# Telemetry_mainlayoutVer2.net
KiCad netlist of a schematic drawn in EAGLE
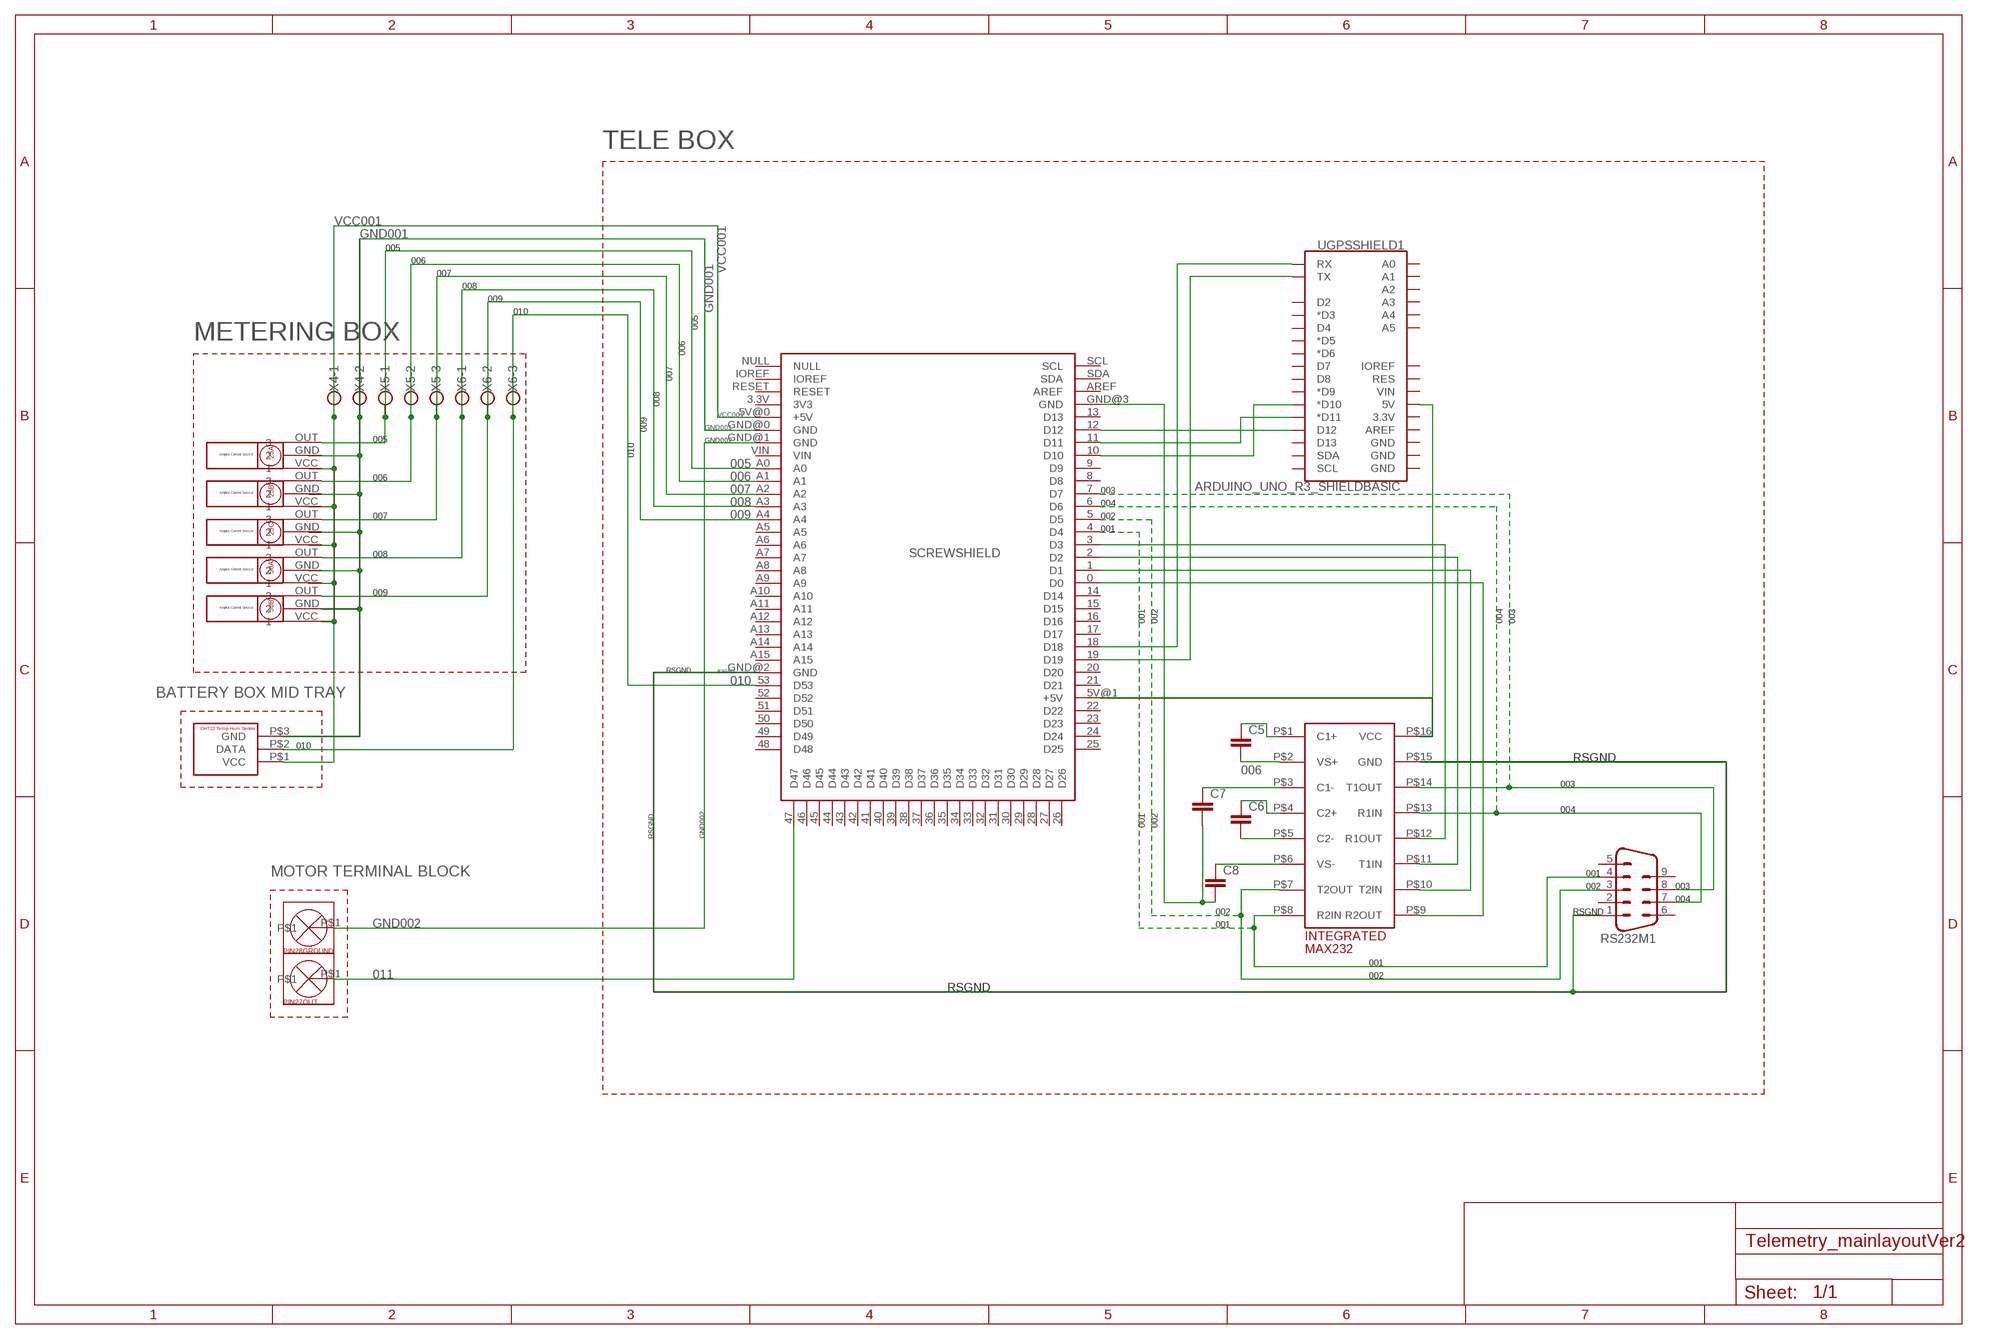
[diagram p0: schematic, sheet 1]

(export (version "E")
  (design (tool "Eeschema 10.0.6"))
  (components
    (comp (ref "25A")
      (value "AMPLOC-CS")
      (footprint "eagle-import:AMPLOC")
      (libsource (lib "eagle-import") (part "AMPLOC-CS"))
    )
    (comp (ref "25B")
      (value "AMPLOC-CS")
      (footprint "eagle-import:AMPLOC")
      (libsource (lib "eagle-import") (part "AMPLOC-CS"))
    )
    (comp (ref "25C")
      (value "AMPLOC-CS")
      (footprint "eagle-import:AMPLOC")
      (libsource (lib "eagle-import") (part "AMPLOC-CS"))
    )
    (comp (ref "50A")
      (value "AMPLOC-CS")
      (footprint "eagle-import:AMPLOC")
      (libsource (lib "eagle-import") (part "AMPLOC-CS"))
    )
    (comp (ref "50B")
      (value "AMPLOC-CS")
      (footprint "eagle-import:AMPLOC")
      (libsource (lib "eagle-import") (part "AMPLOC-CS"))
    )
    (comp (ref "C5")
      (value "C2,5-3")
      (footprint "eagle-import:C2.5-3")
      (libsource (lib "eagle-import") (part "C2,5-3"))
    )
    (comp (ref "C6")
      (value "C2,5-3")
      (footprint "eagle-import:C2.5-3")
      (libsource (lib "eagle-import") (part "C2,5-3"))
    )
    (comp (ref "C7")
      (value "C2,5-3")
      (footprint "eagle-import:C2.5-3")
      (libsource (lib "eagle-import") (part "C2,5-3"))
    )
    (comp (ref "C8")
      (value "C2,5-3")
      (footprint "eagle-import:C2.5-3")
      (libsource (lib "eagle-import") (part "C2,5-3"))
    )
    (comp (ref "INTEGRATED")
      (value "MAX232TELE")
      (footprint "eagle-import:DIP16")
      (libsource (lib "eagle-import") (part "MAX232TELE"))
    )
    (comp (ref "PIN27OUT")
      (value "SCREWTERMINAL")
      (footprint "eagle-import:SCREWTERMINAL")
      (libsource (lib "eagle-import") (part "SCREWTERMINAL"))
    )
    (comp (ref "PIN28GROUND")
      (value "SCREWTERMINAL")
      (footprint "eagle-import:SCREWTERMINAL")
      (libsource (lib "eagle-import") (part "SCREWTERMINAL"))
    )
    (comp (ref "RS232M1")
      (value "M09HP")
      (footprint "eagle-import:M09HP")
      (libsource (lib "eagle-import") (part "M09HP"))
    )
    (comp (ref "SCREWSHIELD")
      (value "PSCREWBPROTOSCREWSHIELD")
      (footprint "eagle-import:ARDUINO_MEGA")
      (libsource (lib "eagle-import") (part "PSCREWBPROTOSCREWSHIELD"))
    )
    (comp (ref "U$8")
      (value "DHT22")
      (footprint "eagle-import:DHT22")
      (libsource (lib "eagle-import") (part "DHT22"))
    )
    (comp (ref "UGPSSHIELD1")
      (value "ARDUINO_UNO_R3_SHIELDBASIC")
      (footprint "eagle-import:UNO_R3_SHIELD")
      (libsource (lib "eagle-import") (part "ARDUINO_UNO_R3_SHIELDBASIC"))
    )
    (comp (ref "X4")
      (value "W237-102")
      (footprint "eagle-import:W237-102")
      (fields (field (name "MPN") "237-102"))
      (libsource (lib "eagle-import") (part "W237-102"))
    )
    (comp (ref "X5")
      (value "W237-103")
      (footprint "eagle-import:W237-103")
      (fields (field (name "MPN") "237-103"))
      (libsource (lib "eagle-import") (part "W237-103"))
    )
    (comp (ref "X6")
      (value "W237-103")
      (footprint "eagle-import:W237-103")
      (fields (field (name "MPN") "237-103"))
      (libsource (lib "eagle-import") (part "W237-103"))
    )
  )
  (nets
    (net (code "1") (name "Net-(25A-1)") (class "Default")
      (node (ref "25A") (pin "VCC") (pinfunction "1_VCC") (pintype "bidirectional"))
      (node (ref "25B") (pin "VCC") (pinfunction "1_VCC") (pintype "bidirectional"))
      (node (ref "25C") (pin "VCC") (pinfunction "1_VCC") (pintype "bidirectional"))
      (node (ref "50A") (pin "VCC") (pinfunction "1_VCC") (pintype "bidirectional"))
      (node (ref "50B") (pin "VCC") (pinfunction "1_VCC") (pintype "bidirectional"))
      (node (ref "SCREWSHIELD") (pin "5V@0") (pinfunction "+5V_5V@0") (pintype "bidirectional"))
      (node (ref "U$8") (pin "P$1") (pinfunction "VCC_P$1") (pintype "bidirectional"))
      (node (ref "X4") (pin "1") (pinfunction "KL_1") (pintype "passive"))
    )
    (net (code "2") (name "Net-(25A-2)") (class "Default")
      (node (ref "25A") (pin "GND") (pinfunction "2_GND") (pintype "bidirectional"))
      (node (ref "25B") (pin "GND") (pinfunction "2_GND") (pintype "bidirectional"))
      (node (ref "25C") (pin "GND") (pinfunction "2_GND") (pintype "bidirectional"))
      (node (ref "50A") (pin "GND") (pinfunction "2_GND") (pintype "bidirectional"))
      (node (ref "50B") (pin "GND") (pinfunction "2_GND") (pintype "bidirectional"))
      (node (ref "SCREWSHIELD") (pin "GND@0") (pinfunction "GND_GND@0") (pintype "bidirectional"))
      (node (ref "U$8") (pin "P$3") (pinfunction "GND_P$3") (pintype "bidirectional"))
      (node (ref "X4") (pin "2") (pinfunction "KL_2") (pintype "passive"))
    )
    (net (code "3") (name "Net-(25A-3)") (class "Default")
      (node (ref "25A") (pin "OUT") (pinfunction "3_OUT") (pintype "bidirectional"))
      (node (ref "SCREWSHIELD") (pin "A0") (pinfunction "A0_A0") (pintype "bidirectional"))
      (node (ref "X5") (pin "1") (pinfunction "KL_1") (pintype "passive"))
    )
    (net (code "4") (name "Net-(25B-3)") (class "Default")
      (node (ref "25B") (pin "OUT") (pinfunction "3_OUT") (pintype "bidirectional"))
      (node (ref "SCREWSHIELD") (pin "A1") (pinfunction "A1_A1") (pintype "bidirectional"))
      (node (ref "X5") (pin "2") (pinfunction "KL_2") (pintype "passive"))
    )
    (net (code "5") (name "Net-(25C-3)") (class "Default")
      (node (ref "25C") (pin "OUT") (pinfunction "3_OUT") (pintype "bidirectional"))
      (node (ref "SCREWSHIELD") (pin "A2") (pinfunction "A2_A2") (pintype "bidirectional"))
      (node (ref "X5") (pin "3") (pinfunction "KL_3") (pintype "passive"))
    )
    (net (code "6") (name "Net-(50A-3)") (class "Default")
      (node (ref "50A") (pin "OUT") (pinfunction "3_OUT") (pintype "bidirectional"))
      (node (ref "SCREWSHIELD") (pin "A3") (pinfunction "A3_A3") (pintype "bidirectional"))
      (node (ref "X6") (pin "1") (pinfunction "KL_1") (pintype "passive"))
    )
    (net (code "7") (name "Net-(50B-3)") (class "Default")
      (node (ref "50B") (pin "OUT") (pinfunction "3_OUT") (pintype "bidirectional"))
      (node (ref "SCREWSHIELD") (pin "A4") (pinfunction "A4_A4") (pintype "bidirectional"))
      (node (ref "X6") (pin "2") (pinfunction "KL_2") (pintype "passive"))
    )
    (net (code "8") (name "Net-(C7-Pad2)") (class "Default")
      (node (ref "C7") (pin "2") (pinfunction "2_2") (pintype "passive"))
      (node (ref "C8") (pin "2") (pinfunction "2_2") (pintype "passive"))
      (node (ref "SCREWSHIELD") (pin "GND@3") (pinfunction "GND_GND@3") (pintype "bidirectional"))
    )
    (net (code "9") (name "Net-(INTEGRATED-C1+)") (class "Default")
      (node (ref "C5") (pin "1") (pinfunction "1_1") (pintype "passive"))
      (node (ref "INTEGRATED") (pin "P$1") (pinfunction "C1+_P$1") (pintype "bidirectional"))
    )
    (net (code "10") (name "Net-(INTEGRATED-C1-)") (class "Default")
      (node (ref "C7") (pin "1") (pinfunction "1_1") (pintype "passive"))
      (node (ref "INTEGRATED") (pin "P$3") (pinfunction "C1-_P$3") (pintype "bidirectional"))
    )
    (net (code "11") (name "Net-(INTEGRATED-C2+)") (class "Default")
      (node (ref "C6") (pin "1") (pinfunction "1_1") (pintype "passive"))
      (node (ref "INTEGRATED") (pin "P$4") (pinfunction "C2+_P$4") (pintype "bidirectional"))
    )
    (net (code "12") (name "Net-(INTEGRATED-C2-)") (class "Default")
      (node (ref "C6") (pin "2") (pinfunction "2_2") (pintype "passive"))
      (node (ref "INTEGRATED") (pin "P$5") (pinfunction "C2-_P$5") (pintype "bidirectional"))
    )
    (net (code "13") (name "Net-(INTEGRATED-GND)") (class "Default")
      (node (ref "INTEGRATED") (pin "P$15") (pinfunction "GND_P$15") (pintype "bidirectional"))
      (node (ref "RS232M1") (pin "1") (pinfunction "1_1") (pintype "passive"))
      (node (ref "SCREWSHIELD") (pin "GND@2") (pinfunction "GND_GND@2") (pintype "bidirectional"))
    )
    (net (code "14") (name "Net-(INTEGRATED-R1IN)") (class "Default")
      (node (ref "INTEGRATED") (pin "P$13") (pinfunction "R1IN_P$13") (pintype "bidirectional"))
      (node (ref "RS232M1") (pin "7") (pinfunction "7_7") (pintype "passive"))
      (node (ref "SCREWSHIELD") (pin "6") (pinfunction "D6_6") (pintype "bidirectional"))
    )
    (net (code "15") (name "Net-(INTEGRATED-R1OUT)") (class "Default")
      (node (ref "INTEGRATED") (pin "P$12") (pinfunction "R1OUT_P$12") (pintype "bidirectional"))
      (node (ref "SCREWSHIELD") (pin "3") (pinfunction "D3_3") (pintype "bidirectional"))
    )
    (net (code "16") (name "Net-(INTEGRATED-R2IN)") (class "Default")
      (node (ref "INTEGRATED") (pin "P$8") (pinfunction "R2IN_P$8") (pintype "bidirectional"))
      (node (ref "RS232M1") (pin "4") (pinfunction "4_4") (pintype "passive"))
      (node (ref "SCREWSHIELD") (pin "4") (pinfunction "D4_4") (pintype "bidirectional"))
    )
    (net (code "17") (name "Net-(INTEGRATED-R2OUT)") (class "Default")
      (node (ref "INTEGRATED") (pin "P$9") (pinfunction "R2OUT_P$9") (pintype "bidirectional"))
      (node (ref "SCREWSHIELD") (pin "0") (pinfunction "D0_0") (pintype "bidirectional"))
    )
    (net (code "18") (name "Net-(INTEGRATED-T1IN)") (class "Default")
      (node (ref "INTEGRATED") (pin "P$11") (pinfunction "T1IN_P$11") (pintype "bidirectional"))
      (node (ref "SCREWSHIELD") (pin "2") (pinfunction "D2_2") (pintype "bidirectional"))
    )
    (net (code "19") (name "Net-(INTEGRATED-T1OUT)") (class "Default")
      (node (ref "INTEGRATED") (pin "P$14") (pinfunction "T1OUT_P$14") (pintype "bidirectional"))
      (node (ref "RS232M1") (pin "8") (pinfunction "8_8") (pintype "passive"))
      (node (ref "SCREWSHIELD") (pin "7") (pinfunction "D7_7") (pintype "bidirectional"))
    )
    (net (code "20") (name "Net-(INTEGRATED-T2IN)") (class "Default")
      (node (ref "INTEGRATED") (pin "P$10") (pinfunction "T2IN_P$10") (pintype "bidirectional"))
      (node (ref "SCREWSHIELD") (pin "1") (pinfunction "D1_1") (pintype "bidirectional"))
    )
    (net (code "21") (name "Net-(INTEGRATED-T2OUT)") (class "Default")
      (node (ref "INTEGRATED") (pin "P$7") (pinfunction "T2OUT_P$7") (pintype "bidirectional"))
      (node (ref "RS232M1") (pin "3") (pinfunction "3_3") (pintype "passive"))
      (node (ref "SCREWSHIELD") (pin "5") (pinfunction "D5_5") (pintype "bidirectional"))
    )
    (net (code "22") (name "Net-(INTEGRATED-VCC)") (class "Default")
      (node (ref "INTEGRATED") (pin "P$16") (pinfunction "VCC_P$16") (pintype "bidirectional"))
      (node (ref "SCREWSHIELD") (pin "5V@1") (pinfunction "+5V_5V@1") (pintype "bidirectional"))
      (node (ref "UGPSSHIELD1") (pin "5V") (pinfunction "5V_5V") (pintype "bidirectional"))
    )
    (net (code "23") (name "Net-(INTEGRATED-VS+)") (class "Default")
      (node (ref "C5") (pin "2") (pinfunction "2_2") (pintype "passive"))
      (node (ref "INTEGRATED") (pin "P$2") (pinfunction "VS+_P$2") (pintype "bidirectional"))
    )
    (net (code "24") (name "Net-(INTEGRATED-VS-)") (class "Default")
      (node (ref "C8") (pin "1") (pinfunction "1_1") (pintype "passive"))
      (node (ref "INTEGRATED") (pin "P$6") (pinfunction "VS-_P$6") (pintype "bidirectional"))
    )
    (net (code "25") (name "Net-(PIN28GROUND-PadP$1)") (class "Default")
      (node (ref "PIN28GROUND") (pin "P$1") (pinfunction "P$1_P$1") (pintype "bidirectional"))
      (node (ref "SCREWSHIELD") (pin "GND@1") (pinfunction "GND_GND@1") (pintype "bidirectional"))
    )
    (net (code "26") (name "Net-(SCREWSHIELD-D10)") (class "Default")
      (node (ref "SCREWSHIELD") (pin "10") (pinfunction "D10_10") (pintype "bidirectional"))
      (node (ref "UGPSSHIELD1") (pin "D10") (pinfunction "*D10_D10") (pintype "bidirectional"))
    )
    (net (code "27") (name "Net-(SCREWSHIELD-D11)") (class "Default")
      (node (ref "SCREWSHIELD") (pin "11") (pinfunction "D11_11") (pintype "bidirectional"))
      (node (ref "UGPSSHIELD1") (pin "D11") (pinfunction "*D11_D11") (pintype "bidirectional"))
    )
    (net (code "28") (name "Net-(SCREWSHIELD-D12)") (class "Default")
      (node (ref "SCREWSHIELD") (pin "12") (pinfunction "D12_12") (pintype "bidirectional"))
      (node (ref "UGPSSHIELD1") (pin "D12") (pinfunction "D12_D12") (pintype "bidirectional"))
    )
    (net (code "29") (name "Net-(SCREWSHIELD-D18)") (class "Default")
      (node (ref "SCREWSHIELD") (pin "18") (pinfunction "D18_18") (pintype "bidirectional"))
      (node (ref "UGPSSHIELD1") (pin "RX") (pinfunction "RX_RX") (pintype "bidirectional"))
    )
    (net (code "30") (name "Net-(SCREWSHIELD-D19)") (class "Default")
      (node (ref "SCREWSHIELD") (pin "19") (pinfunction "D19_19") (pintype "bidirectional"))
      (node (ref "UGPSSHIELD1") (pin "TX") (pinfunction "TX_TX") (pintype "bidirectional"))
    )
    (net (code "31") (name "Net-(SCREWSHIELD-D47)") (class "Default")
      (node (ref "PIN27OUT") (pin "P$1") (pinfunction "P$1_P$1") (pintype "bidirectional"))
      (node (ref "SCREWSHIELD") (pin "47") (pinfunction "D47_47") (pintype "bidirectional"))
    )
    (net (code "32") (name "Net-(SCREWSHIELD-D53)") (class "Default")
      (node (ref "SCREWSHIELD") (pin "53") (pinfunction "D53_53") (pintype "bidirectional"))
      (node (ref "U$8") (pin "P$2") (pinfunction "DATA_P$2") (pintype "bidirectional"))
      (node (ref "X6") (pin "3") (pinfunction "KL_3") (pintype "passive"))
    )
    (net (code "33") (name "unconnected-(RS232M1-Pad2)") (class "Default")
      (node (ref "RS232M1") (pin "2") (pinfunction "2_2") (pintype "passive"))
    )
    (net (code "34") (name "unconnected-(RS232M1-Pad5)") (class "Default")
      (node (ref "RS232M1") (pin "5") (pinfunction "5_5") (pintype "passive"))
    )
    (net (code "35") (name "unconnected-(RS232M1-Pad6)") (class "Default")
      (node (ref "RS232M1") (pin "6") (pinfunction "6_6") (pintype "passive"))
    )
    (net (code "36") (name "unconnected-(RS232M1-Pad9)") (class "Default")
      (node (ref "RS232M1") (pin "9") (pinfunction "9_9") (pintype "passive"))
    )
    (net (code "37") (name "unconnected-(SCREWSHIELD-3V3-Pad3.3V)") (class "Default")
      (node (ref "SCREWSHIELD") (pin "3.3V") (pinfunction "3V3_3.3V") (pintype "bidirectional"))
    )
    (net (code "38") (name "unconnected-(SCREWSHIELD-D8-Pad8)") (class "Default")
      (node (ref "SCREWSHIELD") (pin "8") (pinfunction "D8_8") (pintype "bidirectional"))
    )
    (net (code "39") (name "unconnected-(SCREWSHIELD-D9-Pad9)") (class "Default")
      (node (ref "SCREWSHIELD") (pin "9") (pinfunction "D9_9") (pintype "bidirectional"))
    )
    (net (code "40") (name "unconnected-(SCREWSHIELD-D13-Pad13)") (class "Default")
      (node (ref "SCREWSHIELD") (pin "13") (pinfunction "D13_13") (pintype "bidirectional"))
    )
    (net (code "41") (name "unconnected-(SCREWSHIELD-D14-Pad14)") (class "Default")
      (node (ref "SCREWSHIELD") (pin "14") (pinfunction "D14_14") (pintype "bidirectional"))
    )
    (net (code "42") (name "unconnected-(SCREWSHIELD-D15-Pad15)") (class "Default")
      (node (ref "SCREWSHIELD") (pin "15") (pinfunction "D15_15") (pintype "bidirectional"))
    )
    (net (code "43") (name "unconnected-(SCREWSHIELD-D16-Pad16)") (class "Default")
      (node (ref "SCREWSHIELD") (pin "16") (pinfunction "D16_16") (pintype "bidirectional"))
    )
    (net (code "44") (name "unconnected-(SCREWSHIELD-D17-Pad17)") (class "Default")
      (node (ref "SCREWSHIELD") (pin "17") (pinfunction "D17_17") (pintype "bidirectional"))
    )
    (net (code "45") (name "unconnected-(SCREWSHIELD-D20-Pad20)") (class "Default")
      (node (ref "SCREWSHIELD") (pin "20") (pinfunction "D20_20") (pintype "bidirectional"))
    )
    (net (code "46") (name "unconnected-(SCREWSHIELD-D21-Pad21)") (class "Default")
      (node (ref "SCREWSHIELD") (pin "21") (pinfunction "D21_21") (pintype "bidirectional"))
    )
    (net (code "47") (name "unconnected-(SCREWSHIELD-D22-Pad22)") (class "Default")
      (node (ref "SCREWSHIELD") (pin "22") (pinfunction "D22_22") (pintype "bidirectional"))
    )
    (net (code "48") (name "unconnected-(SCREWSHIELD-D23-Pad23)") (class "Default")
      (node (ref "SCREWSHIELD") (pin "23") (pinfunction "D23_23") (pintype "bidirectional"))
    )
    (net (code "49") (name "unconnected-(SCREWSHIELD-D24-Pad24)") (class "Default")
      (node (ref "SCREWSHIELD") (pin "24") (pinfunction "D24_24") (pintype "bidirectional"))
    )
    (net (code "50") (name "unconnected-(SCREWSHIELD-D25-Pad25)") (class "Default")
      (node (ref "SCREWSHIELD") (pin "25") (pinfunction "D25_25") (pintype "bidirectional"))
    )
    (net (code "51") (name "unconnected-(SCREWSHIELD-D26-Pad26)") (class "Default")
      (node (ref "SCREWSHIELD") (pin "26") (pinfunction "D26_26") (pintype "bidirectional"))
    )
    (net (code "52") (name "unconnected-(SCREWSHIELD-D27-Pad27)") (class "Default")
      (node (ref "SCREWSHIELD") (pin "27") (pinfunction "D27_27") (pintype "bidirectional"))
    )
    (net (code "53") (name "unconnected-(SCREWSHIELD-D28-Pad28)") (class "Default")
      (node (ref "SCREWSHIELD") (pin "28") (pinfunction "D28_28") (pintype "bidirectional"))
    )
    (net (code "54") (name "unconnected-(SCREWSHIELD-D29-Pad29)") (class "Default")
      (node (ref "SCREWSHIELD") (pin "29") (pinfunction "D29_29") (pintype "bidirectional"))
    )
    (net (code "55") (name "unconnected-(SCREWSHIELD-D30-Pad30)") (class "Default")
      (node (ref "SCREWSHIELD") (pin "30") (pinfunction "D30_30") (pintype "bidirectional"))
    )
    (net (code "56") (name "unconnected-(SCREWSHIELD-D31-Pad31)") (class "Default")
      (node (ref "SCREWSHIELD") (pin "31") (pinfunction "D31_31") (pintype "bidirectional"))
    )
    (net (code "57") (name "unconnected-(SCREWSHIELD-D32-Pad32)") (class "Default")
      (node (ref "SCREWSHIELD") (pin "32") (pinfunction "D32_32") (pintype "bidirectional"))
    )
    (net (code "58") (name "unconnected-(SCREWSHIELD-D33-Pad33)") (class "Default")
      (node (ref "SCREWSHIELD") (pin "33") (pinfunction "D33_33") (pintype "bidirectional"))
    )
    (net (code "59") (name "unconnected-(SCREWSHIELD-D34-Pad34)") (class "Default")
      (node (ref "SCREWSHIELD") (pin "34") (pinfunction "D34_34") (pintype "bidirectional"))
    )
    (net (code "60") (name "unconnected-(SCREWSHIELD-D35-Pad35)") (class "Default")
      (node (ref "SCREWSHIELD") (pin "35") (pinfunction "D35_35") (pintype "bidirectional"))
    )
    (net (code "61") (name "unconnected-(SCREWSHIELD-D36-Pad36)") (class "Default")
      (node (ref "SCREWSHIELD") (pin "36") (pinfunction "D36_36") (pintype "bidirectional"))
    )
    (net (code "62") (name "unconnected-(SCREWSHIELD-D37-Pad37)") (class "Default")
      (node (ref "SCREWSHIELD") (pin "37") (pinfunction "D37_37") (pintype "bidirectional"))
    )
    (net (code "63") (name "unconnected-(SCREWSHIELD-D38-Pad38)") (class "Default")
      (node (ref "SCREWSHIELD") (pin "38") (pinfunction "D38_38") (pintype "bidirectional"))
    )
    (net (code "64") (name "unconnected-(SCREWSHIELD-D39-Pad39)") (class "Default")
      (node (ref "SCREWSHIELD") (pin "39") (pinfunction "D39_39") (pintype "bidirectional"))
    )
    (net (code "65") (name "unconnected-(SCREWSHIELD-D40-Pad40)") (class "Default")
      (node (ref "SCREWSHIELD") (pin "40") (pinfunction "D40_40") (pintype "bidirectional"))
    )
    (net (code "66") (name "unconnected-(SCREWSHIELD-D41-Pad41)") (class "Default")
      (node (ref "SCREWSHIELD") (pin "41") (pinfunction "D41_41") (pintype "bidirectional"))
    )
    (net (code "67") (name "unconnected-(SCREWSHIELD-D42-Pad42)") (class "Default")
      (node (ref "SCREWSHIELD") (pin "42") (pinfunction "D42_42") (pintype "bidirectional"))
    )
    (net (code "68") (name "unconnected-(SCREWSHIELD-D43-Pad43)") (class "Default")
      (node (ref "SCREWSHIELD") (pin "43") (pinfunction "D43_43") (pintype "bidirectional"))
    )
    (net (code "69") (name "unconnected-(SCREWSHIELD-D44-Pad44)") (class "Default")
      (node (ref "SCREWSHIELD") (pin "44") (pinfunction "D44_44") (pintype "bidirectional"))
    )
    (net (code "70") (name "unconnected-(SCREWSHIELD-D45-Pad45)") (class "Default")
      (node (ref "SCREWSHIELD") (pin "45") (pinfunction "D45_45") (pintype "bidirectional"))
    )
    (net (code "71") (name "unconnected-(SCREWSHIELD-D46-Pad46)") (class "Default")
      (node (ref "SCREWSHIELD") (pin "46") (pinfunction "D46_46") (pintype "bidirectional"))
    )
    (net (code "72") (name "unconnected-(SCREWSHIELD-D48-Pad48)") (class "Default")
      (node (ref "SCREWSHIELD") (pin "48") (pinfunction "D48_48") (pintype "bidirectional"))
    )
    (net (code "73") (name "unconnected-(SCREWSHIELD-D49-Pad49)") (class "Default")
      (node (ref "SCREWSHIELD") (pin "49") (pinfunction "D49_49") (pintype "bidirectional"))
    )
    (net (code "74") (name "unconnected-(SCREWSHIELD-D50-Pad50)") (class "Default")
      (node (ref "SCREWSHIELD") (pin "50") (pinfunction "D50_50") (pintype "bidirectional"))
    )
    (net (code "75") (name "unconnected-(SCREWSHIELD-D51-Pad51)") (class "Default")
      (node (ref "SCREWSHIELD") (pin "51") (pinfunction "D51_51") (pintype "bidirectional"))
    )
    (net (code "76") (name "unconnected-(SCREWSHIELD-D52-Pad52)") (class "Default")
      (node (ref "SCREWSHIELD") (pin "52") (pinfunction "D52_52") (pintype "bidirectional"))
    )
    (net (code "77") (name "unconnected-(SCREWSHIELD-PadA5)") (class "Default")
      (node (ref "SCREWSHIELD") (pin "A5") (pinfunction "A5_A5") (pintype "bidirectional"))
    )
    (net (code "78") (name "unconnected-(SCREWSHIELD-PadA6)") (class "Default")
      (node (ref "SCREWSHIELD") (pin "A6") (pinfunction "A6_A6") (pintype "bidirectional"))
    )
    (net (code "79") (name "unconnected-(SCREWSHIELD-PadA7)") (class "Default")
      (node (ref "SCREWSHIELD") (pin "A7") (pinfunction "A7_A7") (pintype "bidirectional"))
    )
    (net (code "80") (name "unconnected-(SCREWSHIELD-PadA8)") (class "Default")
      (node (ref "SCREWSHIELD") (pin "A8") (pinfunction "A8_A8") (pintype "bidirectional"))
    )
    (net (code "81") (name "unconnected-(SCREWSHIELD-PadA9)") (class "Default")
      (node (ref "SCREWSHIELD") (pin "A9") (pinfunction "A9_A9") (pintype "bidirectional"))
    )
    (net (code "82") (name "unconnected-(SCREWSHIELD-PadA10)") (class "Default")
      (node (ref "SCREWSHIELD") (pin "A10") (pinfunction "A10_A10") (pintype "bidirectional"))
    )
    (net (code "83") (name "unconnected-(SCREWSHIELD-PadA11)") (class "Default")
      (node (ref "SCREWSHIELD") (pin "A11") (pinfunction "A11_A11") (pintype "bidirectional"))
    )
    (net (code "84") (name "unconnected-(SCREWSHIELD-PadA12)") (class "Default")
      (node (ref "SCREWSHIELD") (pin "A12") (pinfunction "A12_A12") (pintype "bidirectional"))
    )
    (net (code "85") (name "unconnected-(SCREWSHIELD-PadA13)") (class "Default")
      (node (ref "SCREWSHIELD") (pin "A13") (pinfunction "A13_A13") (pintype "bidirectional"))
    )
    (net (code "86") (name "unconnected-(SCREWSHIELD-PadA14)") (class "Default")
      (node (ref "SCREWSHIELD") (pin "A14") (pinfunction "A14_A14") (pintype "bidirectional"))
    )
    (net (code "87") (name "unconnected-(SCREWSHIELD-PadA15)") (class "Default")
      (node (ref "SCREWSHIELD") (pin "A15") (pinfunction "A15_A15") (pintype "bidirectional"))
    )
    (net (code "88") (name "unconnected-(SCREWSHIELD-PadAREF)") (class "Default")
      (node (ref "SCREWSHIELD") (pin "AREF") (pinfunction "AREF_AREF") (pintype "bidirectional"))
    )
    (net (code "89") (name "unconnected-(SCREWSHIELD-PadIOREF)") (class "Default")
      (node (ref "SCREWSHIELD") (pin "IOREF") (pinfunction "IOREF_IOREF") (pintype "bidirectional"))
    )
    (net (code "90") (name "unconnected-(SCREWSHIELD-PadNULL)") (class "Default")
      (node (ref "SCREWSHIELD") (pin "NULL") (pinfunction "NULL_NULL") (pintype "bidirectional"))
    )
    (net (code "91") (name "unconnected-(SCREWSHIELD-PadRESET)") (class "Default")
      (node (ref "SCREWSHIELD") (pin "RESET") (pinfunction "RESET_RESET") (pintype "bidirectional"))
    )
    (net (code "92") (name "unconnected-(SCREWSHIELD-PadSCL)") (class "Default")
      (node (ref "SCREWSHIELD") (pin "SCL") (pinfunction "SCL_SCL") (pintype "bidirectional"))
    )
    (net (code "93") (name "unconnected-(SCREWSHIELD-PadSDA)") (class "Default")
      (node (ref "SCREWSHIELD") (pin "SDA") (pinfunction "SDA_SDA") (pintype "bidirectional"))
    )
    (net (code "94") (name "unconnected-(SCREWSHIELD-PadVIN)") (class "Default")
      (node (ref "SCREWSHIELD") (pin "VIN") (pinfunction "VIN_VIN") (pintype "bidirectional"))
    )
    (net (code "95") (name "unconnected-(UGPSSHIELD1-*D3-PadD3)") (class "Default")
      (node (ref "UGPSSHIELD1") (pin "D3") (pinfunction "*D3_D3") (pintype "bidirectional"))
    )
    (net (code "96") (name "unconnected-(UGPSSHIELD1-*D5-PadD5)") (class "Default")
      (node (ref "UGPSSHIELD1") (pin "D5") (pinfunction "*D5_D5") (pintype "bidirectional"))
    )
    (net (code "97") (name "unconnected-(UGPSSHIELD1-*D6-PadD6)") (class "Default")
      (node (ref "UGPSSHIELD1") (pin "D6") (pinfunction "*D6_D6") (pintype "bidirectional"))
    )
    (net (code "98") (name "unconnected-(UGPSSHIELD1-*D9-PadD9)") (class "Default")
      (node (ref "UGPSSHIELD1") (pin "D9") (pinfunction "*D9_D9") (pintype "bidirectional"))
    )
    (net (code "99") (name "unconnected-(UGPSSHIELD1-GND-PadGND@0)") (class "Default")
      (node (ref "UGPSSHIELD1") (pin "GND@0") (pinfunction "GND_GND@0") (pintype "bidirectional"))
    )
    (net (code "100") (name "unconnected-(UGPSSHIELD1-GND-PadGND@1)") (class "Default")
      (node (ref "UGPSSHIELD1") (pin "GND@1") (pinfunction "GND_GND@1") (pintype "bidirectional"))
    )
    (net (code "101") (name "unconnected-(UGPSSHIELD1-GND-PadGND@2)") (class "Default")
      (node (ref "UGPSSHIELD1") (pin "GND@2") (pinfunction "GND_GND@2") (pintype "bidirectional"))
    )
    (net (code "102") (name "unconnected-(UGPSSHIELD1-Pad3.3V)") (class "Default")
      (node (ref "UGPSSHIELD1") (pin "3.3V") (pinfunction "3.3V_3.3V") (pintype "bidirectional"))
    )
    (net (code "103") (name "unconnected-(UGPSSHIELD1-PadA0)") (class "Default")
      (node (ref "UGPSSHIELD1") (pin "A0") (pinfunction "A0_A0") (pintype "bidirectional"))
    )
    (net (code "104") (name "unconnected-(UGPSSHIELD1-PadA1)") (class "Default")
      (node (ref "UGPSSHIELD1") (pin "A1") (pinfunction "A1_A1") (pintype "bidirectional"))
    )
    (net (code "105") (name "unconnected-(UGPSSHIELD1-PadA2)") (class "Default")
      (node (ref "UGPSSHIELD1") (pin "A2") (pinfunction "A2_A2") (pintype "bidirectional"))
    )
    (net (code "106") (name "unconnected-(UGPSSHIELD1-PadA3)") (class "Default")
      (node (ref "UGPSSHIELD1") (pin "A3") (pinfunction "A3_A3") (pintype "bidirectional"))
    )
    (net (code "107") (name "unconnected-(UGPSSHIELD1-PadA4)") (class "Default")
      (node (ref "UGPSSHIELD1") (pin "A4") (pinfunction "A4_A4") (pintype "bidirectional"))
    )
    (net (code "108") (name "unconnected-(UGPSSHIELD1-PadA5)") (class "Default")
      (node (ref "UGPSSHIELD1") (pin "A5") (pinfunction "A5_A5") (pintype "bidirectional"))
    )
    (net (code "109") (name "unconnected-(UGPSSHIELD1-PadAREF)") (class "Default")
      (node (ref "UGPSSHIELD1") (pin "AREF") (pinfunction "AREF_AREF") (pintype "bidirectional"))
    )
    (net (code "110") (name "unconnected-(UGPSSHIELD1-PadD2)") (class "Default")
      (node (ref "UGPSSHIELD1") (pin "D2") (pinfunction "D2_D2") (pintype "bidirectional"))
    )
    (net (code "111") (name "unconnected-(UGPSSHIELD1-PadD4)") (class "Default")
      (node (ref "UGPSSHIELD1") (pin "D4") (pinfunction "D4_D4") (pintype "bidirectional"))
    )
    (net (code "112") (name "unconnected-(UGPSSHIELD1-PadD7)") (class "Default")
      (node (ref "UGPSSHIELD1") (pin "D7") (pinfunction "D7_D7") (pintype "bidirectional"))
    )
    (net (code "113") (name "unconnected-(UGPSSHIELD1-PadD8)") (class "Default")
      (node (ref "UGPSSHIELD1") (pin "D8") (pinfunction "D8_D8") (pintype "bidirectional"))
    )
    (net (code "114") (name "unconnected-(UGPSSHIELD1-PadD13)") (class "Default")
      (node (ref "UGPSSHIELD1") (pin "D13") (pinfunction "D13_D13") (pintype "bidirectional"))
    )
    (net (code "115") (name "unconnected-(UGPSSHIELD1-PadIOREF)") (class "Default")
      (node (ref "UGPSSHIELD1") (pin "IOREF") (pinfunction "IOREF_IOREF") (pintype "bidirectional"))
    )
    (net (code "116") (name "unconnected-(UGPSSHIELD1-PadRES)") (class "Default")
      (node (ref "UGPSSHIELD1") (pin "RES") (pinfunction "RES_RES") (pintype "bidirectional"))
    )
    (net (code "117") (name "unconnected-(UGPSSHIELD1-PadSCL)") (class "Default")
      (node (ref "UGPSSHIELD1") (pin "SCL") (pinfunction "SCL_SCL") (pintype "bidirectional"))
    )
    (net (code "118") (name "unconnected-(UGPSSHIELD1-PadSDA)") (class "Default")
      (node (ref "UGPSSHIELD1") (pin "SDA") (pinfunction "SDA_SDA") (pintype "bidirectional"))
    )
    (net (code "119") (name "unconnected-(UGPSSHIELD1-PadVIN)") (class "Default")
      (node (ref "UGPSSHIELD1") (pin "VIN") (pinfunction "VIN_VIN") (pintype "bidirectional"))
    )
  )
)
